# powerled.net
KiCad netlist of a schematic drawn in EAGLE
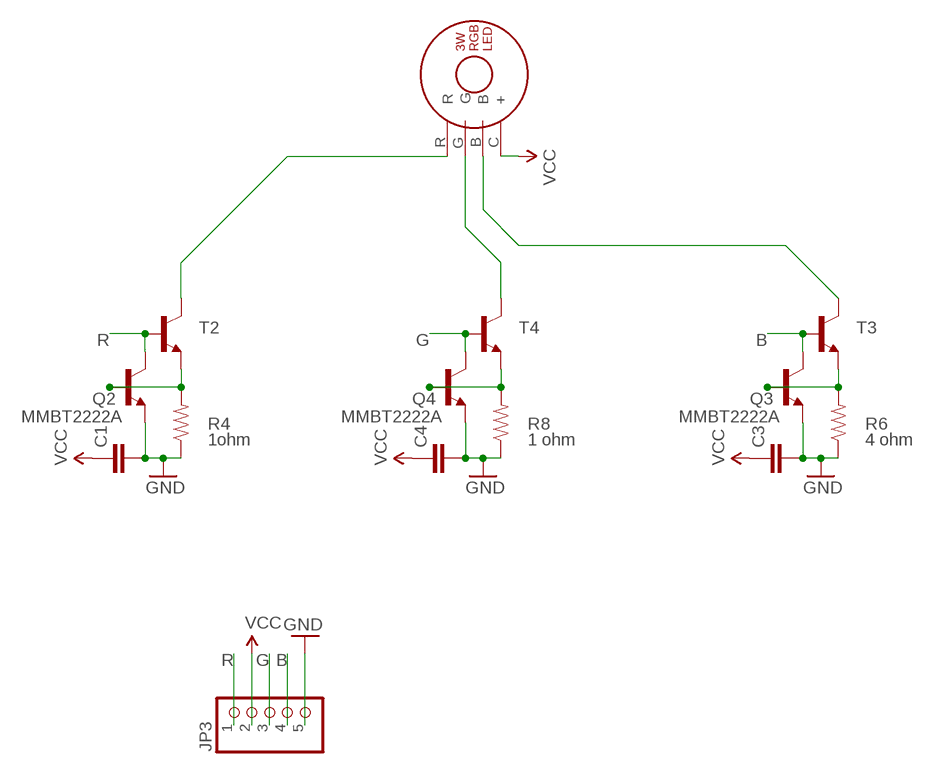
[diagram p0: schematic, sheet 1]

(export (version "E")
  (design (tool "Eeschema 10.0.6"))
  (components
    (comp (ref "C1")
      (value "SPARKFUN_CAP0603-CAP")
      (footprint "eagle-import:SPARKFUN_0603-CAP")
      (libsource (lib "eagle-import") (part "SPARKFUN_CAP0603-CAP"))
    )
    (comp (ref "C3")
      (value "SPARKFUN_CAP0603-CAP")
      (footprint "eagle-import:SPARKFUN_0603-CAP")
      (libsource (lib "eagle-import") (part "SPARKFUN_CAP0603-CAP"))
    )
    (comp (ref "C4")
      (value "SPARKFUN_CAP0603-CAP")
      (footprint "eagle-import:SPARKFUN_0603-CAP")
      (libsource (lib "eagle-import") (part "SPARKFUN_CAP0603-CAP"))
    )
    (comp (ref "JP3")
      (value "PINHD-1X5")
      (footprint "eagle-import:1X05")
      (libsource (lib "eagle-import") (part "PINHD-1X5"))
    )
    (comp (ref "Q2")
      (value "MMBT2222A")
      (footprint "eagle-import:SOT23-3")
      (libsource (lib "eagle-import") (part "TRANSISTOR_NPNMMBT2222A"))
    )
    (comp (ref "Q3")
      (value "MMBT2222A")
      (footprint "eagle-import:SOT23-3")
      (libsource (lib "eagle-import") (part "TRANSISTOR_NPNMMBT2222A"))
    )
    (comp (ref "Q4")
      (value "MMBT2222A")
      (footprint "eagle-import:SOT23-3")
      (libsource (lib "eagle-import") (part "TRANSISTOR_NPNMMBT2222A"))
    )
    (comp (ref "R4")
      (value "1ohm")
      (footprint "eagle-import:0603-RES")
      (libsource (lib "eagle-import") (part "RESISTOR0603-RES"))
    )
    (comp (ref "R6")
      (value "4 ohm")
      (footprint "eagle-import:0603-RES")
      (libsource (lib "eagle-import") (part "RESISTOR0603-RES"))
    )
    (comp (ref "R8")
      (value "1 ohm")
      (footprint "eagle-import:0603-RES")
      (libsource (lib "eagle-import") (part "RESISTOR0603-RES"))
    )
    (comp (ref "T2")
      (value "BCX54-NPN-SOT89-BCE")
      (footprint "eagle-import:SOT89-BCE")
      (libsource (lib "eagle-import") (part "-NPN-SOT89-BCEBCX54"))
    )
    (comp (ref "T3")
      (value "BCX54-NPN-SOT89-BCE")
      (footprint "eagle-import:SOT89-BCE")
      (libsource (lib "eagle-import") (part "-NPN-SOT89-BCEBCX54"))
    )
    (comp (ref "T4")
      (value "BCX54-NPN-SOT89-BCE")
      (footprint "eagle-import:SOT89-BCE")
      (libsource (lib "eagle-import") (part "-NPN-SOT89-BCEBCX54"))
    )
    (comp (ref "U$1")
      (value "RGB3W")
      (footprint "eagle-import:RGB3W")
      (libsource (lib "eagle-import") (part "RGB3W"))
    )
  )
  (nets
    (net (code "1") (name "/B") (class "Default")
      (node (ref "JP3") (pin "4") (pinfunction "4_4") (pintype "passive"))
      (node (ref "Q3") (pin "3") (pinfunction "C_3") (pintype "passive"))
      (node (ref "T3") (pin "B") (pinfunction "B_B") (pintype "passive"))
    )
    (net (code "2") (name "/G") (class "Default")
      (node (ref "JP3") (pin "3") (pinfunction "3_3") (pintype "passive"))
      (node (ref "Q4") (pin "3") (pinfunction "C_3") (pintype "passive"))
      (node (ref "T4") (pin "B") (pinfunction "B_B") (pintype "passive"))
    )
    (net (code "3") (name "/R") (class "Default")
      (node (ref "JP3") (pin "1") (pinfunction "1_1") (pintype "passive"))
      (node (ref "Q2") (pin "3") (pinfunction "C_3") (pintype "passive"))
      (node (ref "T2") (pin "B") (pinfunction "B_B") (pintype "passive"))
    )
    (net (code "4") (name "GND") (class "Default")
      (node (ref "C1") (pin "2") (pinfunction "2_2") (pintype "passive"))
      (node (ref "C3") (pin "2") (pinfunction "2_2") (pintype "passive"))
      (node (ref "C4") (pin "2") (pinfunction "2_2") (pintype "passive"))
      (node (ref "JP3") (pin "5") (pinfunction "5_5") (pintype "passive"))
      (node (ref "Q2") (pin "2") (pinfunction "E_2") (pintype "passive"))
      (node (ref "Q3") (pin "2") (pinfunction "E_2") (pintype "passive"))
      (node (ref "Q4") (pin "2") (pinfunction "E_2") (pintype "passive"))
      (node (ref "R4") (pin "1") (pinfunction "1_1") (pintype "passive"))
      (node (ref "R6") (pin "1") (pinfunction "1_1") (pintype "passive"))
      (node (ref "R8") (pin "1") (pinfunction "1_1") (pintype "passive"))
    )
    (net (code "5") (name "Net-(Q2-B)") (class "Default")
      (node (ref "Q2") (pin "1") (pinfunction "B_1") (pintype "passive"))
      (node (ref "R4") (pin "2") (pinfunction "2_2") (pintype "passive"))
      (node (ref "T2") (pin "E") (pinfunction "E_E") (pintype "passive"))
    )
    (net (code "6") (name "Net-(Q3-B)") (class "Default")
      (node (ref "Q3") (pin "1") (pinfunction "B_1") (pintype "passive"))
      (node (ref "R6") (pin "2") (pinfunction "2_2") (pintype "passive"))
      (node (ref "T3") (pin "E") (pinfunction "E_E") (pintype "passive"))
    )
    (net (code "7") (name "Net-(Q4-B)") (class "Default")
      (node (ref "Q4") (pin "1") (pinfunction "B_1") (pintype "passive"))
      (node (ref "R8") (pin "2") (pinfunction "2_2") (pintype "passive"))
      (node (ref "T4") (pin "E") (pinfunction "E_E") (pintype "passive"))
    )
    (net (code "8") (name "Net-(T2-PadC)") (class "Default")
      (node (ref "T2") (pin "C") (pinfunction "C_C") (pintype "passive"))
      (node (ref "U$1") (pin "R") (pinfunction "R_R") (pintype "bidirectional"))
    )
    (net (code "9") (name "Net-(T3-PadC)") (class "Default")
      (node (ref "T3") (pin "C") (pinfunction "C_C") (pintype "passive"))
      (node (ref "U$1") (pin "B") (pinfunction "B_B") (pintype "bidirectional"))
    )
    (net (code "10") (name "Net-(T4-PadC)") (class "Default")
      (node (ref "T4") (pin "C") (pinfunction "C_C") (pintype "passive"))
      (node (ref "U$1") (pin "G") (pinfunction "G_G") (pintype "bidirectional"))
    )
    (net (code "11") (name "VCC") (class "Default")
      (node (ref "C1") (pin "1") (pinfunction "1_1") (pintype "passive"))
      (node (ref "C3") (pin "1") (pinfunction "1_1") (pintype "passive"))
      (node (ref "C4") (pin "1") (pinfunction "1_1") (pintype "passive"))
      (node (ref "JP3") (pin "2") (pinfunction "2_2") (pintype "passive"))
      (node (ref "U$1") (pin "C") (pinfunction "+_C") (pintype "bidirectional"))
    )
  )
)
